# TCRT500_Sensors.net
KiCad netlist of a schematic drawn in Altium Designer
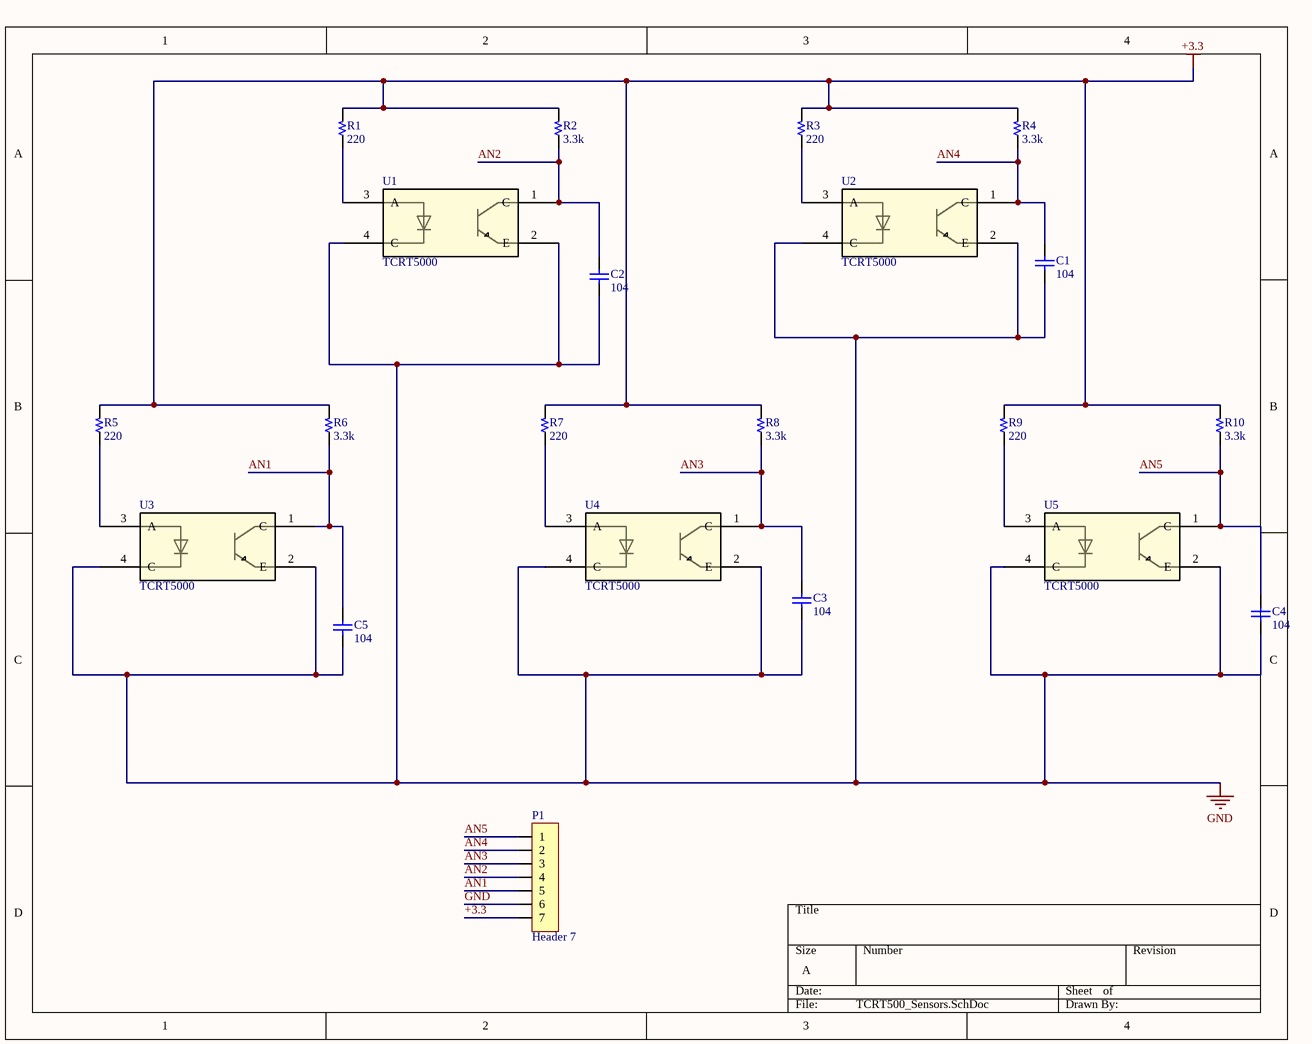
[diagram p0: TCRT500_Sensors.SchDoc]

(export (version "E")
  (design (tool "Eeschema 10.0.6"))
  (components
    (comp (ref "C1")
      (value "104")
      (footprint "CAP Ceramic/W200")
      (description "Capacitor non-pol")
      (libsource (lib "chipfc_altium_libs") (part "Capacitor NP"))
    )
    (comp (ref "C2")
      (value "104")
      (footprint "CAP Ceramic/W200")
      (description "Capacitor non-pol")
      (libsource (lib "chipfc_altium_libs") (part "Capacitor NP"))
    )
    (comp (ref "C3")
      (value "104")
      (footprint "CAP Ceramic/W200")
      (description "Capacitor non-pol")
      (libsource (lib "chipfc_altium_libs") (part "Capacitor NP"))
    )
    (comp (ref "C4")
      (value "104")
      (footprint "CAP Ceramic/W200")
      (description "Capacitor non-pol")
      (libsource (lib "chipfc_altium_libs") (part "Capacitor NP"))
    )
    (comp (ref "C5")
      (value "104")
      (footprint "CAP Ceramic/W200")
      (description "Capacitor non-pol")
      (libsource (lib "chipfc_altium_libs") (part "Capacitor NP"))
    )
    (comp (ref "P1")
      (value "Header 7")
      (footprint "HDR/Header/7")
      (description "Header, 7-Pin")
      (libsource (lib "chipfc_altium_libs") (part "Header 7"))
    )
    (comp (ref "R1")
      (value "220")
      (footprint "R 1/4W/300")
      (description "Resistor")
      (libsource (lib "chipfc_altium_libs") (part "Resistor"))
    )
    (comp (ref "R2")
      (value "3.3k")
      (footprint "R 1/4W/300")
      (description "Resistor")
      (libsource (lib "chipfc_altium_libs") (part "Resistor"))
    )
    (comp (ref "R3")
      (value "220")
      (footprint "R 1/4W/300")
      (description "Resistor")
      (libsource (lib "chipfc_altium_libs") (part "Resistor"))
    )
    (comp (ref "R4")
      (value "3.3k")
      (footprint "R 1/4W/300")
      (description "Resistor")
      (libsource (lib "chipfc_altium_libs") (part "Resistor"))
    )
    (comp (ref "R5")
      (value "220")
      (footprint "R 1/4W/300")
      (description "Resistor")
      (libsource (lib "chipfc_altium_libs") (part "Resistor"))
    )
    (comp (ref "R6")
      (value "3.3k")
      (footprint "R 1/4W/300")
      (description "Resistor")
      (libsource (lib "chipfc_altium_libs") (part "Resistor"))
    )
    (comp (ref "R7")
      (value "220")
      (footprint "R 1/4W/300")
      (description "Resistor")
      (libsource (lib "chipfc_altium_libs") (part "Resistor"))
    )
    (comp (ref "R8")
      (value "3.3k")
      (footprint "R 1/4W/300")
      (description "Resistor")
      (libsource (lib "chipfc_altium_libs") (part "Resistor"))
    )
    (comp (ref "R9")
      (value "220")
      (footprint "R 1/4W/300")
      (description "Resistor")
      (libsource (lib "chipfc_altium_libs") (part "Resistor"))
    )
    (comp (ref "R10")
      (value "3.3k")
      (footprint "R 1/4W/300")
      (description "Resistor")
      (libsource (lib "chipfc_altium_libs") (part "Resistor"))
    )
    (comp (ref "U1")
      (value "TCRT5000")
      (footprint "TCRT5000")
      (description "SENSOR REFL, LENSES, CONVER. AXES-e2")
      (fields (field (name "COPYRIGHT") "Copyright (C) 2025 Ultra Librarian. All rights reserved."))
      (libsource (lib "NGHIA") (part "TCRT5000"))
    )
    (comp (ref "U2")
      (value "TCRT5000")
      (footprint "TCRT5000")
      (description "SENSOR REFL, LENSES, CONVER. AXES-e2")
      (fields (field (name "COPYRIGHT") "Copyright (C) 2025 Ultra Librarian. All rights reserved."))
      (libsource (lib "NGHIA") (part "TCRT5000"))
    )
    (comp (ref "U3")
      (value "TCRT5000")
      (footprint "TCRT5000")
      (description "SENSOR REFL, LENSES, CONVER. AXES-e2")
      (fields (field (name "COPYRIGHT") "Copyright (C) 2025 Ultra Librarian. All rights reserved."))
      (libsource (lib "NGHIA") (part "TCRT5000"))
    )
    (comp (ref "U4")
      (value "TCRT5000")
      (footprint "TCRT5000")
      (description "SENSOR REFL, LENSES, CONVER. AXES-e2")
      (fields (field (name "COPYRIGHT") "Copyright (C) 2025 Ultra Librarian. All rights reserved."))
      (libsource (lib "NGHIA") (part "TCRT5000"))
    )
    (comp (ref "U5")
      (value "TCRT5000")
      (footprint "TCRT5000")
      (description "SENSOR REFL, LENSES, CONVER. AXES-e2")
      (fields (field (name "COPYRIGHT") "Copyright (C) 2025 Ultra Librarian. All rights reserved."))
      (libsource (lib "NGHIA") (part "TCRT5000"))
    )
  )
  (nets
    (net (code "1") (name "+3.3") (class "Default")
      (node (ref "P1") (pin "7") (pinfunction "7_7") (pintype "passive"))
      (node (ref "R1") (pin "2") (pinfunction "2_2") (pintype "passive"))
      (node (ref "R10") (pin "2") (pinfunction "2_2") (pintype "passive"))
      (node (ref "R2") (pin "2") (pinfunction "2_2") (pintype "passive"))
      (node (ref "R3") (pin "2") (pinfunction "2_2") (pintype "passive"))
      (node (ref "R4") (pin "2") (pinfunction "2_2") (pintype "passive"))
      (node (ref "R5") (pin "2") (pinfunction "2_2") (pintype "passive"))
      (node (ref "R6") (pin "2") (pinfunction "2_2") (pintype "passive"))
      (node (ref "R7") (pin "2") (pinfunction "2_2") (pintype "passive"))
      (node (ref "R8") (pin "2") (pinfunction "2_2") (pintype "passive"))
      (node (ref "R9") (pin "2") (pinfunction "2_2") (pintype "passive"))
    )
    (net (code "2") (name "/AN1") (class "Default")
      (node (ref "C5") (pin "1") (pinfunction "1_1") (pintype "passive"))
      (node (ref "P1") (pin "5") (pinfunction "5_5") (pintype "passive"))
      (node (ref "R6") (pin "1") (pinfunction "1_1") (pintype "passive"))
      (node (ref "U3") (pin "1") (pinfunction "C_1") (pintype "passive"))
    )
    (net (code "3") (name "/AN2") (class "Default")
      (node (ref "C2") (pin "1") (pinfunction "1_1") (pintype "passive"))
      (node (ref "P1") (pin "4") (pinfunction "4_4") (pintype "passive"))
      (node (ref "R2") (pin "1") (pinfunction "1_1") (pintype "passive"))
      (node (ref "U1") (pin "1") (pinfunction "C_1") (pintype "passive"))
    )
    (net (code "4") (name "/AN3") (class "Default")
      (node (ref "C3") (pin "1") (pinfunction "1_1") (pintype "passive"))
      (node (ref "P1") (pin "3") (pinfunction "3_3") (pintype "passive"))
      (node (ref "R8") (pin "1") (pinfunction "1_1") (pintype "passive"))
      (node (ref "U4") (pin "1") (pinfunction "C_1") (pintype "passive"))
    )
    (net (code "5") (name "/AN4") (class "Default")
      (node (ref "C1") (pin "1") (pinfunction "1_1") (pintype "passive"))
      (node (ref "P1") (pin "2") (pinfunction "2_2") (pintype "passive"))
      (node (ref "R4") (pin "1") (pinfunction "1_1") (pintype "passive"))
      (node (ref "U2") (pin "1") (pinfunction "C_1") (pintype "passive"))
    )
    (net (code "6") (name "/AN5") (class "Default")
      (node (ref "C4") (pin "1") (pinfunction "1_1") (pintype "passive"))
      (node (ref "P1") (pin "1") (pinfunction "1_1") (pintype "passive"))
      (node (ref "R10") (pin "1") (pinfunction "1_1") (pintype "passive"))
      (node (ref "U5") (pin "1") (pinfunction "C_1") (pintype "passive"))
    )
    (net (code "7") (name "GND") (class "Default")
      (node (ref "C1") (pin "2") (pinfunction "2_2") (pintype "passive"))
      (node (ref "C2") (pin "2") (pinfunction "2_2") (pintype "passive"))
      (node (ref "C3") (pin "2") (pinfunction "2_2") (pintype "passive"))
      (node (ref "C4") (pin "2") (pinfunction "2_2") (pintype "passive"))
      (node (ref "C5") (pin "2") (pinfunction "2_2") (pintype "passive"))
      (node (ref "P1") (pin "6") (pinfunction "6_6") (pintype "passive"))
      (node (ref "U1") (pin "2") (pinfunction "E_2") (pintype "passive"))
      (node (ref "U1") (pin "4") (pinfunction "C_4") (pintype "passive"))
      (node (ref "U2") (pin "2") (pinfunction "E_2") (pintype "passive"))
      (node (ref "U2") (pin "4") (pinfunction "C_4") (pintype "passive"))
      (node (ref "U3") (pin "2") (pinfunction "E_2") (pintype "passive"))
      (node (ref "U3") (pin "4") (pinfunction "C_4") (pintype "passive"))
      (node (ref "U4") (pin "2") (pinfunction "E_2") (pintype "passive"))
      (node (ref "U4") (pin "4") (pinfunction "C_4") (pintype "passive"))
      (node (ref "U5") (pin "2") (pinfunction "E_2") (pintype "passive"))
      (node (ref "U5") (pin "4") (pinfunction "C_4") (pintype "passive"))
    )
    (net (code "8") (name "Net-(U1-A)") (class "Default")
      (node (ref "R1") (pin "1") (pinfunction "1_1") (pintype "passive"))
      (node (ref "U1") (pin "3") (pinfunction "A_3") (pintype "passive"))
    )
    (net (code "9") (name "Net-(U2-A)") (class "Default")
      (node (ref "R3") (pin "1") (pinfunction "1_1") (pintype "passive"))
      (node (ref "U2") (pin "3") (pinfunction "A_3") (pintype "passive"))
    )
    (net (code "10") (name "Net-(U3-A)") (class "Default")
      (node (ref "R5") (pin "1") (pinfunction "1_1") (pintype "passive"))
      (node (ref "U3") (pin "3") (pinfunction "A_3") (pintype "passive"))
    )
    (net (code "11") (name "Net-(U4-A)") (class "Default")
      (node (ref "R7") (pin "1") (pinfunction "1_1") (pintype "passive"))
      (node (ref "U4") (pin "3") (pinfunction "A_3") (pintype "passive"))
    )
    (net (code "12") (name "Net-(U5-A)") (class "Default")
      (node (ref "R9") (pin "1") (pinfunction "1_1") (pintype "passive"))
      (node (ref "U5") (pin "3") (pinfunction "A_3") (pintype "passive"))
    )
  )
)
